# Schematic_RocketTalk_4_6_2021-07-23.net
KiCad netlist of a schematic drawn in EasyEDA
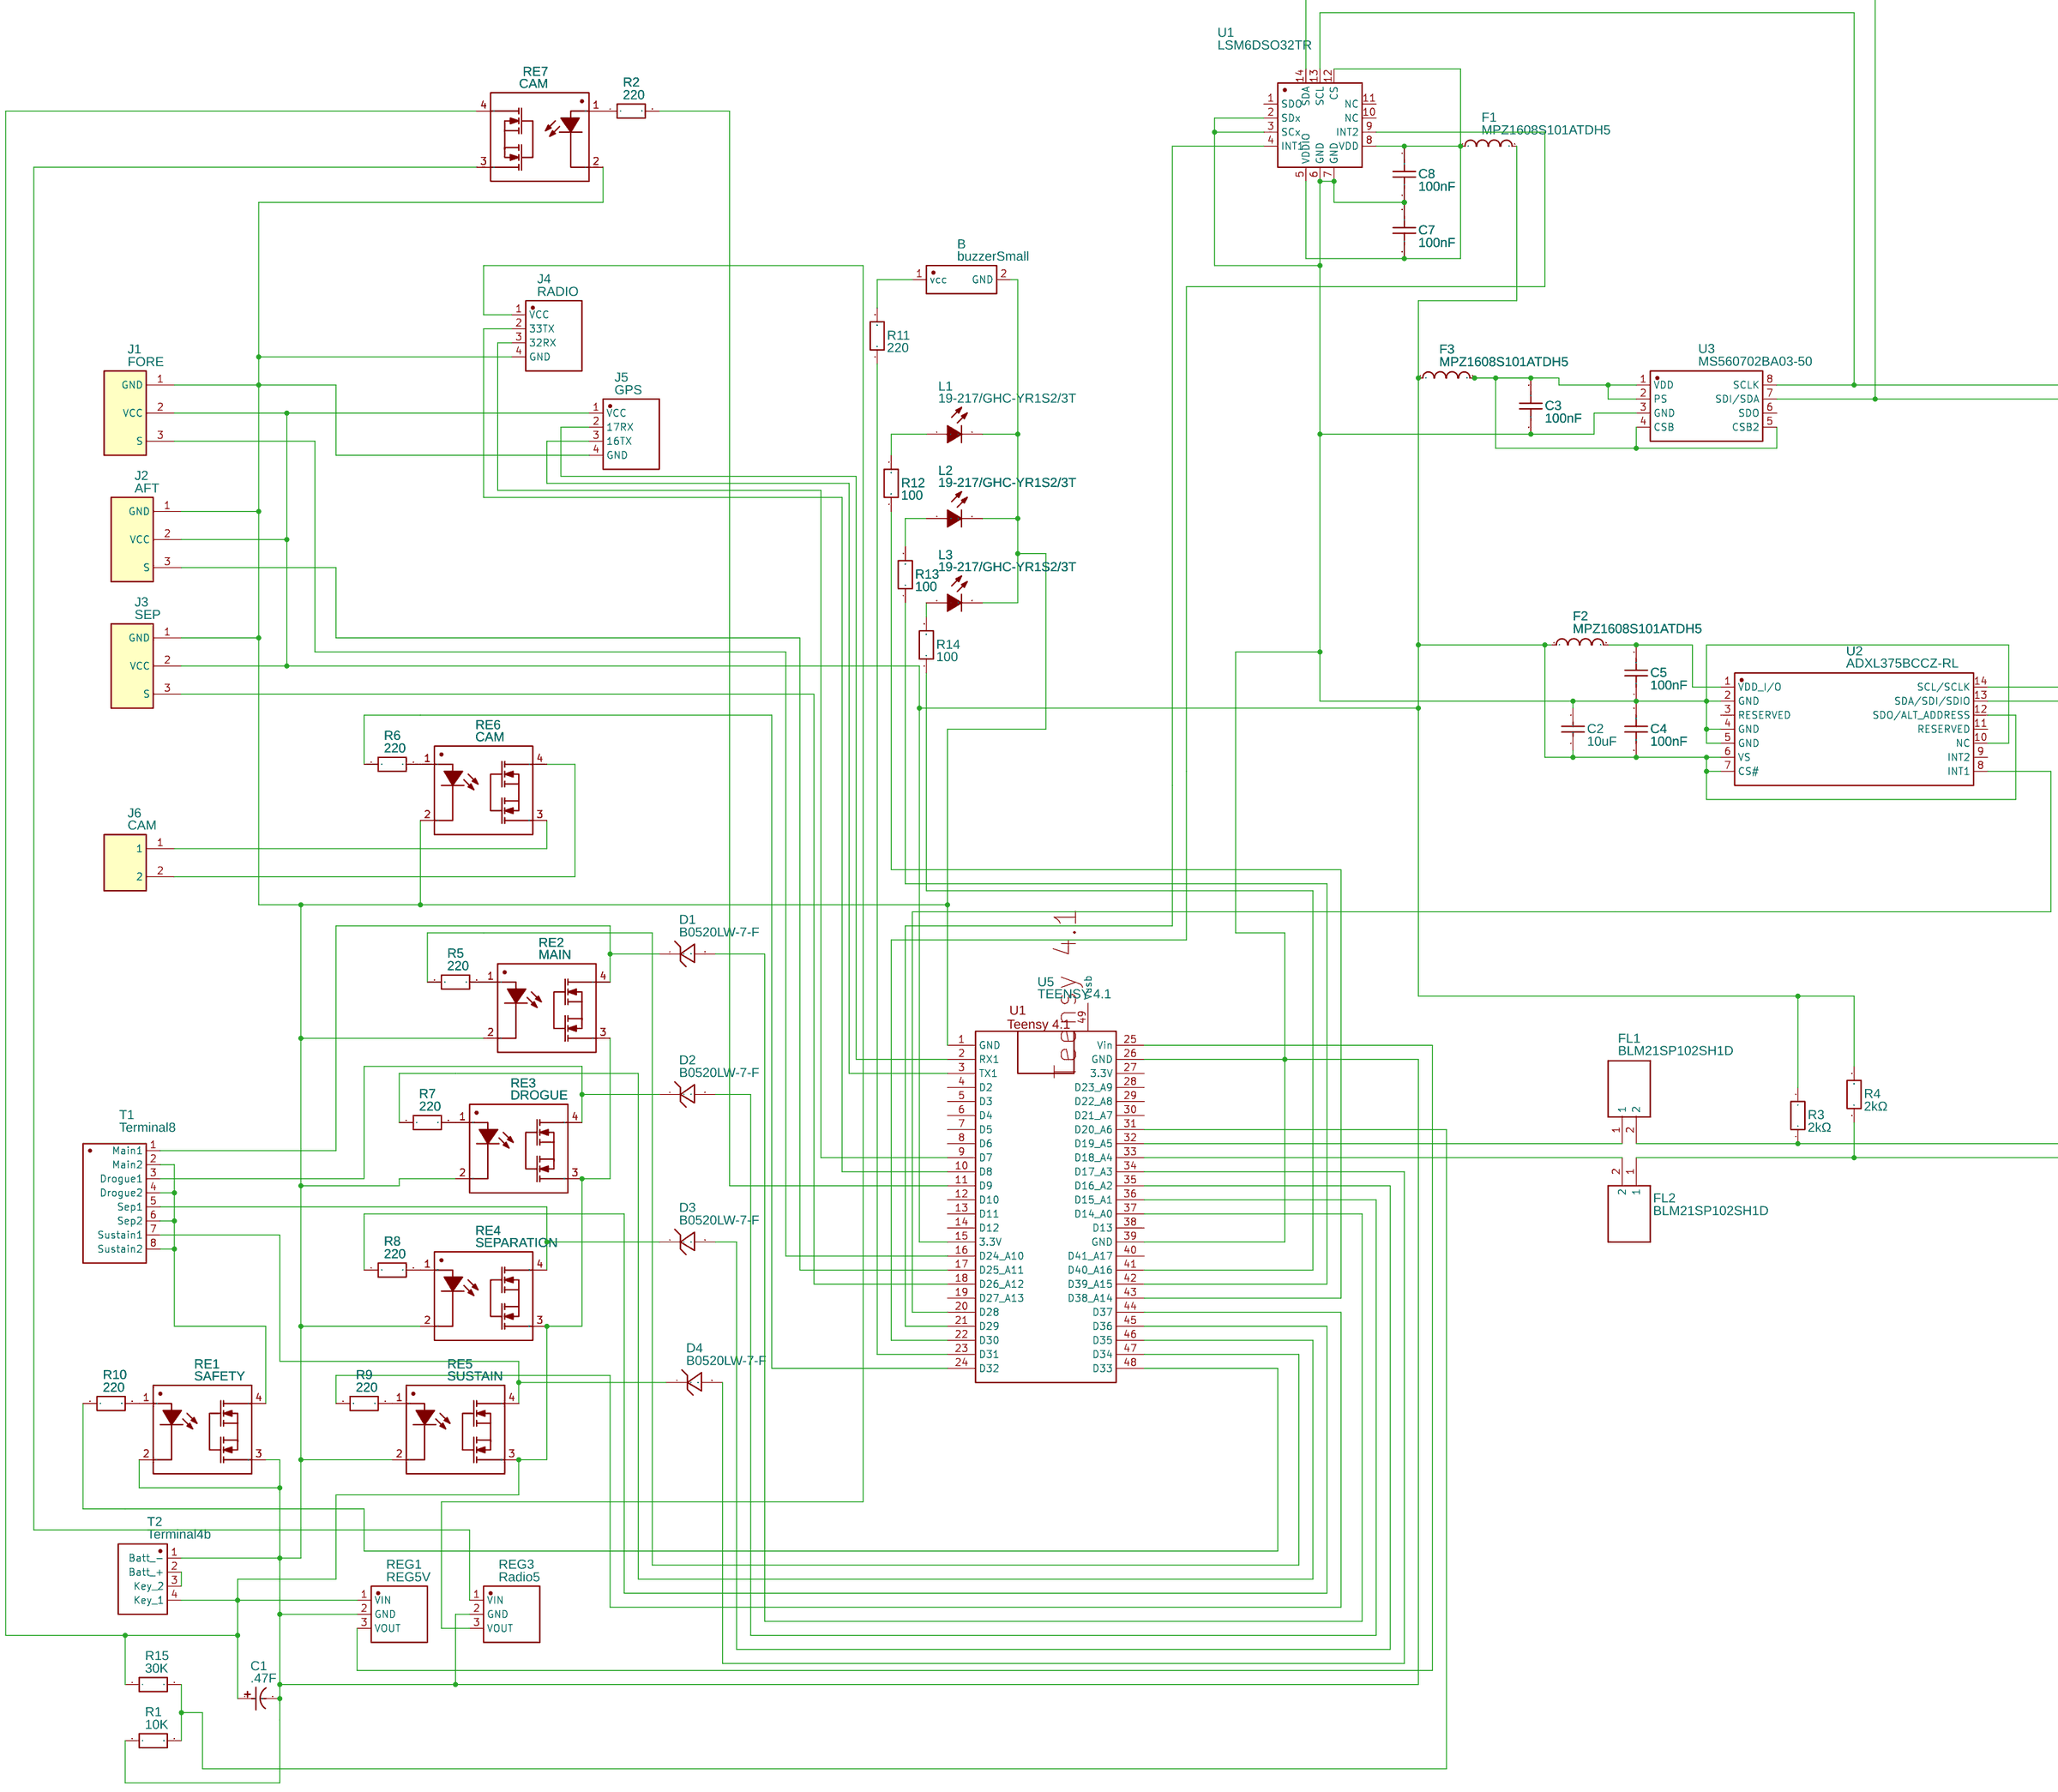
[diagram p0: schematic sheet]

(export (version "E")
  (design (tool "Eeschema 10.0.6"))
  (components
    (comp (ref "B") (value "buzzerSmall") (libsource (lib "") (part "buzzerSmall")))
    (comp (ref "C1")
      (value ".47F")
      (fields
        (field (name "BOM_Manufacturer Part") "SP-5R5-Z224VYA")
        (field (name "BOM_Supplier Part") "C128280")
      )
      (libsource (lib "") (part "SP-5R5-Z224VYA"))
    )
    (comp (ref "C2")
      (value "10uF")
      (fields
        (field (name "BOM_Manufacturer Part") "CL05A106MQ5NUNC")
        (field (name "BOM_Supplier Part") "C15525")
      )
      (libsource (lib "") (part "CL05A106MQ5NUNC"))
    )
    (comp (ref "C3")
      (value "100nF")
      (fields
        (field (name "BOM_Manufacturer Part") "CC0402KRX7R6BB104")
        (field (name "BOM_Supplier Part") "C309458")
      )
      (libsource (lib "") (part "CC0402KRX7R6BB104_1"))
    )
    (comp (ref "C4")
      (value "100nF")
      (fields
        (field (name "BOM_Manufacturer Part") "CC0402KRX7R6BB104")
        (field (name "BOM_Supplier Part") "C309458")
      )
      (libsource (lib "") (part "CC0402KRX7R6BB104"))
    )
    (comp (ref "C5")
      (value "100nF")
      (fields
        (field (name "BOM_Manufacturer Part") "CC0402KRX7R6BB104")
        (field (name "BOM_Supplier Part") "C309458")
      )
      (libsource (lib "") (part "CC0402KRX7R6BB104_1"))
    )
    (comp (ref "C7")
      (value "100nF")
      (fields
        (field (name "BOM_Manufacturer Part") "CC0402KRX7R6BB104")
        (field (name "BOM_Supplier Part") "C309458")
      )
      (libsource (lib "") (part "CC0402KRX7R6BB104"))
    )
    (comp (ref "C8")
      (value "100nF")
      (fields
        (field (name "BOM_Manufacturer Part") "CC0402KRX7R6BB104")
        (field (name "BOM_Supplier Part") "C309458")
      )
      (libsource (lib "") (part "CC0402KRX7R6BB104"))
    )
    (comp (ref "D1")
      (value "B0520LW-7-F")
      (fields (field (name "BOM_Supplier Part") "C155367"))
      (libsource (lib "") (part "B0520LW-7-F"))
    )
    (comp (ref "D2")
      (value "B0520LW-7-F")
      (fields (field (name "BOM_Supplier Part") "C155367"))
      (libsource (lib "") (part "B0520LW-7-F"))
    )
    (comp (ref "D3")
      (value "B0520LW-7-F")
      (fields (field (name "BOM_Supplier Part") "C155367"))
      (libsource (lib "") (part "B0520LW-7-F"))
    )
    (comp (ref "D4")
      (value "B0520LW-7-F")
      (fields (field (name "BOM_Supplier Part") "C155367"))
      (libsource (lib "") (part "B0520LW-7-F"))
    )
    (comp (ref "F1")
      (value "MPZ1608S101ATDH5")
      (fields (field (name "BOM_Supplier Part") "C307769"))
      (libsource (lib "") (part "MPZ1608S101ATDH5"))
    )
    (comp (ref "F2")
      (value "MPZ1608S101ATDH5")
      (fields (field (name "BOM_Supplier Part") "C307769"))
      (libsource (lib "") (part "MPZ1608S101ATDH5"))
    )
    (comp (ref "F3")
      (value "MPZ1608S101ATDH5")
      (fields (field (name "BOM_Supplier Part") "C307769"))
      (libsource (lib "") (part "MPZ1608S101ATDH5"))
    )
    (comp (ref "FL1") (value "BLM21SP102SH1D") (libsource (lib "") (part "BLM21SP102SH1D_1")))
    (comp (ref "FL2") (value "BLM21SP102SH1D") (libsource (lib "") (part "BLM21SP102SH1D")))
    (comp (ref "J1")
      (value "FORE")
      (fields
        (field (name "BOM_Manufacturer Part") "B3B-PH-K-S(LF)(SN)")
        (field (name "BOM_Supplier Part") "C131339")
      )
      (libsource (lib "") (part "Unknown_125_-1020"))
    )
    (comp (ref "J2")
      (value "AFT")
      (fields
        (field (name "BOM_Manufacturer Part") "B3B-PH-K-S(LF)(SN)")
        (field (name "BOM_Supplier Part") "C131339")
      )
      (libsource (lib "") (part "Unknown_130_-930"))
    )
    (comp (ref "J3")
      (value "SEP")
      (fields
        (field (name "BOM_Manufacturer Part") "B3B-PH-K-S(LF)(SN)")
        (field (name "BOM_Supplier Part") "C131339")
      )
      (libsource (lib "") (part "Unknown_130_-840"))
    )
    (comp (ref "J4")
      (value "RADIO")
      (fields
        (field (name "BOM_Manufacturer Part") "B4B-PH-K(LF)(SN)")
        (field (name "BOM_Supplier Part") "C265289")
      )
      (libsource (lib "") (part "Unknown_410_-1080"))
    )
    (comp (ref "J5")
      (value "GPS")
      (fields
        (field (name "BOM_Manufacturer Part") "B4B-PH-K(LF)(SN)")
        (field (name "BOM_Supplier Part") "C265289")
      )
      (libsource (lib "") (part "Unknown_465_-1010"))
    )
    (comp (ref "J6")
      (value "CAM")
      (fields
        (field (name "BOM_Manufacturer Part") "B2B-PH-K-S(LF)(SN)")
        (field (name "BOM_Supplier Part") "C131337")
      )
      (libsource (lib "") (part "B2B-PH-K-S(LF)(SN)"))
    )
    (comp (ref "L1")
      (value "19-217/GHC-YR1S2/3T")
      (fields (field (name "BOM_Supplier Part") "C72043"))
      (libsource (lib "") (part "19-217/GHC-YR1S2/3T"))
    )
    (comp (ref "L2")
      (value "19-217/GHC-YR1S2/3T")
      (fields (field (name "BOM_Supplier Part") "C72043"))
      (libsource (lib "") (part "19-217/GHC-YR1S2/3T"))
    )
    (comp (ref "L3")
      (value "19-217/GHC-YR1S2/3T")
      (fields (field (name "BOM_Supplier Part") "C72043"))
      (libsource (lib "") (part "19-217/GHC-YR1S2/3T"))
    )
    (comp (ref "R1")
      (value "10K")
      (fields
        (field (name "BOM_Manufacturer Part") "ERJP06J221V")
        (field (name "BOM_Supplier Part") "C417010")
      )
      (libsource (lib "") (part "ERJP06J221V"))
    )
    (comp (ref "R2")
      (value "220")
      (fields
        (field (name "BOM_Manufacturer Part") "ERJP06J221V")
        (field (name "BOM_Supplier Part") "C417010")
      )
      (libsource (lib "") (part "ERJP06J221V"))
    )
    (comp (ref "R3")
      (value "2kΩ")
      (fields
        (field (name "BOM_Manufacturer Part") "ERA6AEB202V")
        (field (name "BOM_Supplier Part") "C417117")
      )
      (libsource (lib "") (part "ERA6AEB202V"))
    )
    (comp (ref "R4")
      (value "2kΩ")
      (fields
        (field (name "BOM_Manufacturer Part") "ERA6AEB202V")
        (field (name "BOM_Supplier Part") "C417117")
      )
      (libsource (lib "") (part "ERA6AEB202V"))
    )
    (comp (ref "R5")
      (value "220")
      (fields
        (field (name "BOM_Manufacturer Part") "ERJP06J221V")
        (field (name "BOM_Supplier Part") "C417010")
      )
      (libsource (lib "") (part "ERJP06J221V"))
    )
    (comp (ref "R6")
      (value "220")
      (fields
        (field (name "BOM_Manufacturer Part") "ERJP06J221V")
        (field (name "BOM_Supplier Part") "C417010")
      )
      (libsource (lib "") (part "ERJP06J221V"))
    )
    (comp (ref "R7")
      (value "220")
      (fields
        (field (name "BOM_Manufacturer Part") "ERJP06J221V")
        (field (name "BOM_Supplier Part") "C417010")
      )
      (libsource (lib "") (part "ERJP06J221V"))
    )
    (comp (ref "R8")
      (value "220")
      (fields
        (field (name "BOM_Manufacturer Part") "ERJP06J221V")
        (field (name "BOM_Supplier Part") "C417010")
      )
      (libsource (lib "") (part "ERJP06J221V"))
    )
    (comp (ref "R9")
      (value "220")
      (fields
        (field (name "BOM_Manufacturer Part") "ERJP06J221V")
        (field (name "BOM_Supplier Part") "C417010")
      )
      (libsource (lib "") (part "ERJP06J221V"))
    )
    (comp (ref "R10")
      (value "220")
      (fields
        (field (name "BOM_Manufacturer Part") "ERJP06J221V")
        (field (name "BOM_Supplier Part") "C417010")
      )
      (libsource (lib "") (part "ERJP06J221V"))
    )
    (comp (ref "R11")
      (value "220")
      (fields
        (field (name "BOM_Manufacturer Part") "ERJP06J221V")
        (field (name "BOM_Supplier Part") "C417010")
      )
      (libsource (lib "") (part "ERJP06J221V_1"))
    )
    (comp (ref "R12")
      (value "100")
      (fields
        (field (name "BOM_Manufacturer Part") "ERJP06J221V")
        (field (name "BOM_Supplier Part") "C417010")
      )
      (libsource (lib "") (part "ERJP06J221V_1"))
    )
    (comp (ref "R13")
      (value "100")
      (fields
        (field (name "BOM_Manufacturer Part") "ERJP06J221V")
        (field (name "BOM_Supplier Part") "C417010")
      )
      (libsource (lib "") (part "ERJP06J221V_1"))
    )
    (comp (ref "R14")
      (value "100")
      (fields
        (field (name "BOM_Manufacturer Part") "ERJP06J221V")
        (field (name "BOM_Supplier Part") "C417010")
      )
      (libsource (lib "") (part "ERJP06J221V_1"))
    )
    (comp (ref "R15")
      (value "30K")
      (fields
        (field (name "BOM_Manufacturer Part") "ERJP06J221V")
        (field (name "BOM_Supplier Part") "C417010")
      )
      (libsource (lib "") (part "ERJP06J221V"))
    )
    (comp (ref "RE1")
      (value "SAFETY")
      (fields (field (name "BOM_Manufacturer Part") "AQY210EH") (field (name "BOM_Supplier Part") "C13541"))
      (libsource (lib "") (part "AQY210EH_1"))
    )
    (comp (ref "RE2")
      (value "MAIN")
      (fields (field (name "BOM_Manufacturer Part") "AQY210EH") (field (name "BOM_Supplier Part") "C13541"))
      (libsource (lib "") (part "AQY210EH_1"))
    )
    (comp (ref "RE3")
      (value "DROGUE")
      (fields (field (name "BOM_Manufacturer Part") "AQY210EH") (field (name "BOM_Supplier Part") "C13541"))
      (libsource (lib "") (part "AQY210EH_1"))
    )
    (comp (ref "RE4")
      (value "SEPARATION")
      (fields (field (name "BOM_Manufacturer Part") "AQY210EH") (field (name "BOM_Supplier Part") "C13541"))
      (libsource (lib "") (part "AQY210EH_1"))
    )
    (comp (ref "RE5")
      (value "SUSTAIN")
      (fields (field (name "BOM_Manufacturer Part") "AQY210EH") (field (name "BOM_Supplier Part") "C13541"))
      (libsource (lib "") (part "AQY210EH_1"))
    )
    (comp (ref "RE6")
      (value "CAM")
      (fields (field (name "BOM_Manufacturer Part") "AQY210EH") (field (name "BOM_Supplier Part") "C13541"))
      (libsource (lib "") (part "AQY210EH_1"))
    )
    (comp (ref "RE7")
      (value "CAM")
      (fields (field (name "BOM_Manufacturer Part") "AQY210EH") (field (name "BOM_Supplier Part") "C13541"))
      (libsource (lib "") (part "AQY210EH"))
    )
    (comp (ref "REG1") (value "REG5V") (libsource (lib "") (part "Unknown_310_-165")))
    (comp (ref "REG3") (value "Radio5") (libsource (lib "") (part "Unknown_390_-165")))
    (comp (ref "T1") (value "Terminal8") (libsource (lib "") (part "Terminal8")))
    (comp (ref "T2") (value "Terminal4b") (libsource (lib "") (part "Terminal4b")))
    (comp (ref "U1")
      (value "LSM6DSO32TR")
      (fields (field (name "BOM_Supplier Part") "497-LSM6DSO32TR-ND"))
      (libsource (lib "") (part "LSM6DSO32TR"))
    )
    (comp (ref "U2")
      (value "ADXL375BCCZ-RL")
      (fields (field (name "BOM_Supplier Part") "C662206"))
      (libsource (lib "") (part "ADXL375BCCZ-RL"))
    )
    (comp (ref "U3")
      (value "MS560702BA03-50")
      (fields (field (name "BOM_Supplier Part") "C97627"))
      (libsource (lib "") (part "MS560702BA03-50"))
    )
    (comp (ref "U5") (value "TEENSY 4.1") (libsource (lib "") (part "TEENSY 4.1")))
  )
  (nets
    (net (code "1") (name "Net-(B-GND)") (class "Default")
      (node (ref "B") (pin "2") (pinfunction "GND_2") (pintype "unspecified"))
      (node (ref "C1") (pin "2") (pinfunction "2_2") (pintype "input"))
      (node (ref "C2") (pin "1") (pinfunction "1_1") (pintype "input"))
      (node (ref "C3") (pin "1") (pinfunction "1_1") (pintype "unspecified"))
      (node (ref "C4") (pin "1") (pinfunction "1_1") (pintype "unspecified"))
      (node (ref "C5") (pin "1") (pinfunction "1_1") (pintype "unspecified"))
      (node (ref "C7") (pin "1") (pinfunction "1_1") (pintype "unspecified"))
      (node (ref "C8") (pin "2") (pinfunction "2_2") (pintype "unspecified"))
      (node (ref "J1") (pin "1") (pinfunction "GND_1") (pintype "input"))
      (node (ref "J2") (pin "1") (pinfunction "GND_1") (pintype "input"))
      (node (ref "J3") (pin "1") (pinfunction "GND_1") (pintype "input"))
      (node (ref "J4") (pin "4") (pinfunction "GND_4") (pintype "unspecified"))
      (node (ref "J5") (pin "4") (pinfunction "GND_4") (pintype "unspecified"))
      (node (ref "L1") (pin "2") (pinfunction "C_2") (pintype "input"))
      (node (ref "L2") (pin "2") (pinfunction "C_2") (pintype "input"))
      (node (ref "L3") (pin "2") (pinfunction "C_2") (pintype "input"))
      (node (ref "R1") (pin "1") (pinfunction "1_1") (pintype "unspecified"))
      (node (ref "RE1") (pin "2") (pinfunction "K_2") (pintype "unspecified"))
      (node (ref "RE1") (pin "3") (pinfunction "3_3") (pintype "unspecified"))
      (node (ref "RE2") (pin "2") (pinfunction "K_2") (pintype "unspecified"))
      (node (ref "RE3") (pin "2") (pinfunction "K_2") (pintype "unspecified"))
      (node (ref "RE4") (pin "2") (pinfunction "K_2") (pintype "unspecified"))
      (node (ref "RE5") (pin "2") (pinfunction "K_2") (pintype "unspecified"))
      (node (ref "RE6") (pin "2") (pinfunction "K_2") (pintype "unspecified"))
      (node (ref "RE7") (pin "2") (pinfunction "K_2") (pintype "unspecified"))
      (node (ref "REG1") (pin "2") (pinfunction "GND_2") (pintype "unspecified"))
      (node (ref "REG3") (pin "2") (pinfunction "GND_2") (pintype "unspecified"))
      (node (ref "T2") (pin "1") (pinfunction "Batt_-_1") (pintype "unspecified"))
      (node (ref "U1") (pin "2") (pinfunction "SDx_2") (pintype "unspecified"))
      (node (ref "U1") (pin "3") (pinfunction "SCx_3") (pintype "unspecified"))
      (node (ref "U1") (pin "6") (pinfunction "GND_6") (pintype "unspecified"))
      (node (ref "U1") (pin "7") (pinfunction "GND_7") (pintype "unspecified"))
      (node (ref "U2") (pin "10") (pinfunction "NC_10") (pintype "unspecified"))
      (node (ref "U2") (pin "2") (pinfunction "GND_2") (pintype "unspecified"))
      (node (ref "U2") (pin "4") (pinfunction "GND_4") (pintype "unspecified"))
      (node (ref "U2") (pin "5") (pinfunction "GND_5") (pintype "unspecified"))
      (node (ref "U3") (pin "3") (pinfunction "GND_3") (pintype "unspecified"))
      (node (ref "U5") (pin "1") (pinfunction "GND_1") (pintype "unspecified"))
      (node (ref "U5") (pin "26") (pinfunction "GND_26") (pintype "unspecified"))
      (node (ref "U5") (pin "39") (pinfunction "GND_39") (pintype "unspecified"))
    )
    (net (code "2") (name "Net-(B-vcc)") (class "Default")
      (node (ref "B") (pin "1") (pinfunction "vcc_1") (pintype "unspecified"))
      (node (ref "R11") (pin "2") (pinfunction "2_2") (pintype "unspecified"))
    )
    (net (code "3") (name "Net-(J1-S)") (class "Default")
      (node (ref "J1") (pin "3") (pinfunction "S_3") (pintype "input"))
      (node (ref "U5") (pin "16") (pinfunction "D24_A10_16") (pintype "unspecified"))
    )
    (net (code "4") (name "Net-(J1-VCC)") (class "Default")
      (node (ref "C2") (pin "2") (pinfunction "2_2") (pintype "input"))
      (node (ref "C4") (pin "2") (pinfunction "2_2") (pintype "unspecified"))
      (node (ref "F1") (pin "2") (pinfunction "2_2") (pintype "unspecified"))
      (node (ref "F2") (pin "1") (pinfunction "1_1") (pintype "unspecified"))
      (node (ref "F3") (pin "1") (pinfunction "1_1") (pintype "unspecified"))
      (node (ref "J1") (pin "2") (pinfunction "VCC_2") (pintype "input"))
      (node (ref "J2") (pin "2") (pinfunction "VCC_2") (pintype "input"))
      (node (ref "J3") (pin "2") (pinfunction "VCC_2") (pintype "input"))
      (node (ref "J5") (pin "1") (pinfunction "VCC_1") (pintype "unspecified"))
      (node (ref "R3") (pin "2") (pinfunction "2_2") (pintype "unspecified"))
      (node (ref "R4") (pin "2") (pinfunction "2_2") (pintype "unspecified"))
      (node (ref "U2") (pin "12") (pinfunction "SDO/ALT_ADDRESS_12") (pintype "unspecified"))
      (node (ref "U2") (pin "6") (pinfunction "VS_6") (pintype "unspecified"))
      (node (ref "U2") (pin "7") (pinfunction "CS#_7") (pintype "unspecified"))
      (node (ref "U5") (pin "15") (pinfunction "3.3V_15") (pintype "unspecified"))
    )
    (net (code "5") (name "Net-(J2-S)") (class "Default")
      (node (ref "J2") (pin "3") (pinfunction "S_3") (pintype "input"))
      (node (ref "U5") (pin "17") (pinfunction "D25_A11_17") (pintype "unspecified"))
    )
    (net (code "6") (name "Net-(J3-S)") (class "Default")
      (node (ref "J3") (pin "3") (pinfunction "S_3") (pintype "input"))
      (node (ref "U5") (pin "18") (pinfunction "D26_A12_18") (pintype "unspecified"))
    )
    (net (code "7") (name "Net-(J4-32RX)") (class "Default")
      (node (ref "J4") (pin "3") (pinfunction "32RX_3") (pintype "unspecified"))
      (node (ref "U5") (pin "9") (pinfunction "D7_9") (pintype "unspecified"))
    )
    (net (code "8") (name "Net-(J4-33TX)") (class "Default")
      (node (ref "J4") (pin "2") (pinfunction "33TX_2") (pintype "unspecified"))
      (node (ref "U5") (pin "10") (pinfunction "D8_10") (pintype "unspecified"))
    )
    (net (code "9") (name "Net-(J4-VCC)") (class "Default")
      (node (ref "J4") (pin "1") (pinfunction "VCC_1") (pintype "unspecified"))
      (node (ref "REG3") (pin "3") (pinfunction "VOUT_3") (pintype "unspecified"))
    )
    (net (code "10") (name "Net-(J5-16TX)") (class "Default")
      (node (ref "J5") (pin "3") (pinfunction "16TX_3") (pintype "unspecified"))
      (node (ref "U5") (pin "3") (pinfunction "TX1_3") (pintype "unspecified"))
    )
    (net (code "11") (name "Net-(J5-17RX)") (class "Default")
      (node (ref "J5") (pin "2") (pinfunction "17RX_2") (pintype "unspecified"))
      (node (ref "U5") (pin "2") (pinfunction "RX1_2") (pintype "unspecified"))
    )
    (net (code "12") (name "Net-(J6-Pad1)") (class "Default")
      (node (ref "J6") (pin "1") (pinfunction "1_1") (pintype "input"))
      (node (ref "RE6") (pin "3") (pinfunction "3_3") (pintype "unspecified"))
    )
    (net (code "13") (name "Net-(J6-Pad2)") (class "Default")
      (node (ref "J6") (pin "2") (pinfunction "2_2") (pintype "input"))
      (node (ref "RE6") (pin "4") (pinfunction "4_4") (pintype "unspecified"))
    )
    (net (code "14") (name "Net-(L1-A)") (class "Default")
      (node (ref "L1") (pin "1") (pinfunction "A_1") (pintype "input"))
      (node (ref "R12") (pin "2") (pinfunction "2_2") (pintype "unspecified"))
    )
    (net (code "15") (name "Net-(L2-A)") (class "Default")
      (node (ref "L2") (pin "1") (pinfunction "A_1") (pintype "input"))
      (node (ref "R13") (pin "2") (pinfunction "2_2") (pintype "unspecified"))
    )
    (net (code "16") (name "Net-(L3-A)") (class "Default")
      (node (ref "L3") (pin "1") (pinfunction "A_1") (pintype "input"))
      (node (ref "R14") (pin "2") (pinfunction "2_2") (pintype "unspecified"))
    )
    (net (code "17") (name "Net-(R2-Pad1)") (class "Default")
      (node (ref "R2") (pin "1") (pinfunction "1_1") (pintype "unspecified"))
      (node (ref "RE7") (pin "1") (pinfunction "1_1") (pintype "unspecified"))
    )
    (net (code "18") (name "Net-(R5-Pad2)") (class "Default")
      (node (ref "R5") (pin "2") (pinfunction "2_2") (pintype "unspecified"))
      (node (ref "RE2") (pin "1") (pinfunction "1_1") (pintype "unspecified"))
    )
    (net (code "19") (name "Net-(R6-Pad2)") (class "Default")
      (node (ref "R6") (pin "2") (pinfunction "2_2") (pintype "unspecified"))
      (node (ref "RE6") (pin "1") (pinfunction "1_1") (pintype "unspecified"))
    )
    (net (code "20") (name "Net-(R7-Pad2)") (class "Default")
      (node (ref "R7") (pin "2") (pinfunction "2_2") (pintype "unspecified"))
      (node (ref "RE3") (pin "1") (pinfunction "1_1") (pintype "unspecified"))
    )
    (net (code "21") (name "Net-(R8-Pad2)") (class "Default")
      (node (ref "R8") (pin "2") (pinfunction "2_2") (pintype "unspecified"))
      (node (ref "RE4") (pin "1") (pinfunction "1_1") (pintype "unspecified"))
    )
    (net (code "22") (name "Net-(R9-Pad2)") (class "Default")
      (node (ref "R9") (pin "2") (pinfunction "2_2") (pintype "unspecified"))
      (node (ref "RE5") (pin "1") (pinfunction "1_1") (pintype "unspecified"))
    )
    (net (code "23") (name "Net-(R10-Pad2)") (class "Default")
      (node (ref "R10") (pin "2") (pinfunction "2_2") (pintype "unspecified"))
      (node (ref "RE1") (pin "1") (pinfunction "1_1") (pintype "unspecified"))
    )
    (net (code "24") (name "Net-(REG1-VIN)") (class "Default")
      (node (ref "C1") (pin "1") (pinfunction "1_1") (pintype "input"))
      (node (ref "R15") (pin "1") (pinfunction "1_1") (pintype "unspecified"))
      (node (ref "RE2") (pin "3") (pinfunction "3_3") (pintype "unspecified"))
      (node (ref "RE3") (pin "3") (pinfunction "3_3") (pintype "unspecified"))
      (node (ref "RE4") (pin "3") (pinfunction "3_3") (pintype "unspecified"))
      (node (ref "RE5") (pin "3") (pinfunction "3_3") (pintype "unspecified"))
      (node (ref "RE7") (pin "4") (pinfunction "4_4") (pintype "unspecified"))
      (node (ref "REG1") (pin "1") (pinfunction "VIN_1") (pintype "unspecified"))
      (node (ref "T2") (pin "4") (pinfunction "Key_1_4") (pintype "unspecified"))
    )
    (net (code "25") (name "Net-(REG1-VOUT)") (class "Default")
      (node (ref "REG1") (pin "3") (pinfunction "VOUT_3") (pintype "unspecified"))
      (node (ref "U5") (pin "25") (pinfunction "Vin_25") (pintype "unspecified"))
    )
    (net (code "26") (name "Net-(REG3-VIN)") (class "Default")
      (node (ref "RE7") (pin "3") (pinfunction "3_3") (pintype "unspecified"))
      (node (ref "REG3") (pin "1") (pinfunction "VIN_1") (pintype "unspecified"))
    )
    (net (code "27") (name "Net-(T1-Drogue1)") (class "Default")
      (node (ref "D2") (pin "1") (pinfunction "1_1") (pintype "unspecified"))
      (node (ref "RE3") (pin "4") (pinfunction "4_4") (pintype "unspecified"))
      (node (ref "T1") (pin "3") (pinfunction "Drogue1_3") (pintype "unspecified"))
    )
    (net (code "28") (name "Net-(T1-Drogue2)") (class "Default")
      (node (ref "RE1") (pin "4") (pinfunction "4_4") (pintype "unspecified"))
      (node (ref "T1") (pin "2") (pinfunction "Main2_2") (pintype "unspecified"))
      (node (ref "T1") (pin "4") (pinfunction "Drogue2_4") (pintype "unspecified"))
      (node (ref "T1") (pin "6") (pinfunction "Sep2_6") (pintype "unspecified"))
      (node (ref "T1") (pin "8") (pinfunction "Sustain2_8") (pintype "unspecified"))
    )
    (net (code "29") (name "Net-(T1-Main1)") (class "Default")
      (node (ref "D1") (pin "1") (pinfunction "1_1") (pintype "unspecified"))
      (node (ref "RE2") (pin "4") (pinfunction "4_4") (pintype "unspecified"))
      (node (ref "T1") (pin "1") (pinfunction "Main1_1") (pintype "unspecified"))
    )
    (net (code "30") (name "Net-(T1-Sep1)") (class "Default")
      (node (ref "D3") (pin "1") (pinfunction "1_1") (pintype "unspecified"))
      (node (ref "RE4") (pin "4") (pinfunction "4_4") (pintype "unspecified"))
      (node (ref "T1") (pin "5") (pinfunction "Sep1_5") (pintype "unspecified"))
    )
    (net (code "31") (name "Net-(T1-Sustain1)") (class "Default")
      (node (ref "D4") (pin "1") (pinfunction "1_1") (pintype "unspecified"))
      (node (ref "RE5") (pin "4") (pinfunction "4_4") (pintype "unspecified"))
      (node (ref "T1") (pin "7") (pinfunction "Sustain1_7") (pintype "unspecified"))
    )
    (net (code "32") (name "Net-(T2-Batt_+)") (class "Default")
      (node (ref "T2") (pin "2") (pinfunction "Batt_+_2") (pintype "unspecified"))
      (node (ref "T2") (pin "3") (pinfunction "Key_2_3") (pintype "unspecified"))
    )
    (net (code "33") (name "Net-(U1-CS)") (class "Default")
      (node (ref "C7") (pin "2") (pinfunction "2_2") (pintype "unspecified"))
      (node (ref "C8") (pin "1") (pinfunction "1_1") (pintype "unspecified"))
      (node (ref "F1") (pin "1") (pinfunction "1_1") (pintype "unspecified"))
      (node (ref "U1") (pin "12") (pinfunction "CS_12") (pintype "unspecified"))
      (node (ref "U1") (pin "5") (pinfunction "VDDIO_5") (pintype "unspecified"))
      (node (ref "U1") (pin "8") (pinfunction "VDD_8") (pintype "unspecified"))
    )
    (net (code "34") (name "Net-(U1-INT1)") (class "Default")
      (node (ref "U1") (pin "4") (pinfunction "INT1_4") (pintype "unspecified"))
      (node (ref "U5") (pin "21") (pinfunction "D29_21") (pintype "unspecified"))
    )
    (net (code "35") (name "Net-(U1-INT2)") (class "Default")
      (node (ref "U1") (pin "9") (pinfunction "INT2_9") (pintype "unspecified"))
      (node (ref "U5") (pin "22") (pinfunction "D30_22") (pintype "unspecified"))
    )
    (net (code "36") (name "Net-(U1-SCL)") (class "Default")
      (node (ref "FL1") (pin "2") (pinfunction "2_2") (pintype "bidirectional"))
      (node (ref "R3") (pin "1") (pinfunction "1_1") (pintype "unspecified"))
      (node (ref "U1") (pin "13") (pinfunction "SCL_13") (pintype "unspecified"))
      (node (ref "U2") (pin "14") (pinfunction "SCL/SCLK_14") (pintype "unspecified"))
      (node (ref "U3") (pin "8") (pinfunction "SCLK_8") (pintype "unspecified"))
    )
    (net (code "37") (name "Net-(U1-SDA)") (class "Default")
      (node (ref "FL2") (pin "1") (pinfunction "1_1") (pintype "bidirectional"))
      (node (ref "R4") (pin "1") (pinfunction "1_1") (pintype "unspecified"))
      (node (ref "U1") (pin "14") (pinfunction "SDA_14") (pintype "unspecified"))
      (node (ref "U2") (pin "13") (pinfunction "SDA/SDI/SDIO_13") (pintype "unspecified"))
      (node (ref "U3") (pin "7") (pinfunction "SDI/SDA_7") (pintype "unspecified"))
    )
    (net (code "38") (name "Net-(U2-INT1)") (class "Default")
      (node (ref "U2") (pin "8") (pinfunction "INT1_8") (pintype "unspecified"))
      (node (ref "U5") (pin "20") (pinfunction "D28_20") (pintype "unspecified"))
    )
    (net (code "39") (name "Net-(U2-VDD_I{slash}O)") (class "Default")
      (node (ref "C5") (pin "2") (pinfunction "2_2") (pintype "unspecified"))
      (node (ref "F2") (pin "2") (pinfunction "2_2") (pintype "unspecified"))
      (node (ref "U2") (pin "1") (pinfunction "VDD_I/O_1") (pintype "unspecified"))
    )
    (net (code "40") (name "Net-(U3-CSB)") (class "Default")
      (node (ref "C3") (pin "2") (pinfunction "2_2") (pintype "unspecified"))
      (node (ref "F3") (pin "2") (pinfunction "2_2") (pintype "unspecified"))
      (node (ref "U3") (pin "1") (pinfunction "VDD_1") (pintype "unspecified"))
      (node (ref "U3") (pin "2") (pinfunction "PS_2") (pintype "unspecified"))
      (node (ref "U3") (pin "4") (pinfunction "CSB_4") (pintype "unspecified"))
      (node (ref "U3") (pin "5") (pinfunction "CSB2_5") (pintype "unspecified"))
    )
    (net (code "41") (name "Net-(U5-D9)") (class "Default")
      (node (ref "R2") (pin "2") (pinfunction "2_2") (pintype "unspecified"))
      (node (ref "U5") (pin "11") (pinfunction "D9_11") (pintype "unspecified"))
    )
    (net (code "42") (name "Net-(U5-D14_A0)") (class "Default")
      (node (ref "D1") (pin "2") (pinfunction "2_2") (pintype "unspecified"))
      (node (ref "U5") (pin "37") (pinfunction "D14_A0_37") (pintype "unspecified"))
    )
    (net (code "43") (name "Net-(U5-D15_A1)") (class "Default")
      (node (ref "D2") (pin "2") (pinfunction "2_2") (pintype "unspecified"))
      (node (ref "U5") (pin "36") (pinfunction "D15_A1_36") (pintype "unspecified"))
    )
    (net (code "44") (name "Net-(U5-D16_A2)") (class "Default")
      (node (ref "D3") (pin "2") (pinfunction "2_2") (pintype "unspecified"))
      (node (ref "U5") (pin "35") (pinfunction "D16_A2_35") (pintype "unspecified"))
    )
    (net (code "45") (name "Net-(U5-D17_A3)") (class "Default")
      (node (ref "D4") (pin "2") (pinfunction "2_2") (pintype "unspecified"))
      (node (ref "U5") (pin "34") (pinfunction "D17_A3_34") (pintype "unspecified"))
    )
    (net (code "46") (name "Net-(U5-D18_A4)") (class "Default")
      (node (ref "FL2") (pin "2") (pinfunction "2_2") (pintype "bidirectional"))
      (node (ref "U5") (pin "33") (pinfunction "D18_A4_33") (pintype "unspecified"))
    )
    (net (code "47") (name "Net-(U5-D19_A5)") (class "Default")
      (node (ref "FL1") (pin "1") (pinfunction "1_1") (pintype "bidirectional"))
      (node (ref "U5") (pin "32") (pinfunction "D19_A5_32") (pintype "unspecified"))
    )
    (net (code "48") (name "Net-(U5-D20_A6)") (class "Default")
      (node (ref "R1") (pin "2") (pinfunction "2_2") (pintype "unspecified"))
      (node (ref "R15") (pin "2") (pinfunction "2_2") (pintype "unspecified"))
      (node (ref "U5") (pin "31") (pinfunction "D20_A6_31") (pintype "unspecified"))
    )
    (net (code "49") (name "Net-(U5-D31)") (class "Default")
      (node (ref "R11") (pin "1") (pinfunction "1_1") (pintype "unspecified"))
      (node (ref "U5") (pin "23") (pinfunction "D31_23") (pintype "unspecified"))
    )
    (net (code "50") (name "Net-(U5-D32)") (class "Default")
      (node (ref "R6") (pin "1") (pinfunction "1_1") (pintype "unspecified"))
      (node (ref "U5") (pin "24") (pinfunction "D32_24") (pintype "unspecified"))
    )
    (net (code "51") (name "Net-(U5-D33)") (class "Default")
      (node (ref "R10") (pin "1") (pinfunction "1_1") (pintype "unspecified"))
      (node (ref "U5") (pin "48") (pinfunction "D33_48") (pintype "unspecified"))
    )
    (net (code "52") (name "Net-(U5-D34)") (class "Default")
      (node (ref "R5") (pin "1") (pinfunction "1_1") (pintype "unspecified"))
      (node (ref "U5") (pin "47") (pinfunction "D34_47") (pintype "unspecified"))
    )
    (net (code "53") (name "Net-(U5-D35)") (class "Default")
      (node (ref "R7") (pin "1") (pinfunction "1_1") (pintype "unspecified"))
      (node (ref "U5") (pin "46") (pinfunction "D35_46") (pintype "unspecified"))
    )
    (net (code "54") (name "Net-(U5-D36)") (class "Default")
      (node (ref "R8") (pin "1") (pinfunction "1_1") (pintype "unspecified"))
      (node (ref "U5") (pin "45") (pinfunction "D36_45") (pintype "unspecified"))
    )
    (net (code "55") (name "Net-(U5-D37)") (class "Default")
      (node (ref "R9") (pin "1") (pinfunction "1_1") (pintype "unspecified"))
      (node (ref "U5") (pin "44") (pinfunction "D37_44") (pintype "unspecified"))
    )
    (net (code "56") (name "Net-(U5-D38_A14)") (class "Default")
      (node (ref "R12") (pin "1") (pinfunction "1_1") (pintype "unspecified"))
      (node (ref "U5") (pin "43") (pinfunction "D38_A14_43") (pintype "unspecified"))
    )
    (net (code "57") (name "Net-(U5-D39_A15)") (class "Default")
      (node (ref "R13") (pin "1") (pinfunction "1_1") (pintype "unspecified"))
      (node (ref "U5") (pin "42") (pinfunction "D39_A15_42") (pintype "unspecified"))
    )
    (net (code "58") (name "Net-(U5-D40_A16)") (class "Default")
      (node (ref "R14") (pin "1") (pinfunction "1_1") (pintype "unspecified"))
      (node (ref "U5") (pin "41") (pinfunction "D40_A16_41") (pintype "unspecified"))
    )
    (net (code "59") (name "unconnected-(U1-NC-Pad10)") (class "Default")
      (node (ref "U1") (pin "10") (pinfunction "NC_10") (pintype "unspecified"))
    )
    (net (code "60") (name "unconnected-(U1-NC-Pad11)") (class "Default")
      (node (ref "U1") (pin "11") (pinfunction "NC_11") (pintype "unspecified"))
    )
    (net (code "61") (name "unconnected-(U1-SDO-Pad1)") (class "Default")
      (node (ref "U1") (pin "1") (pinfunction "SDO_1") (pintype "unspecified"))
    )
    (net (code "62") (name "unconnected-(U2-INT2-Pad9)") (class "Default")
      (node (ref "U2") (pin "9") (pinfunction "INT2_9") (pintype "unspecified"))
    )
    (net (code "63") (name "unconnected-(U2-RESERVED-Pad3)") (class "Default")
      (node (ref "U2") (pin "3") (pinfunction "RESERVED_3") (pintype "unspecified"))
    )
    (net (code "64") (name "unconnected-(U2-RESERVED-Pad11)") (class "Default")
      (node (ref "U2") (pin "11") (pinfunction "RESERVED_11") (pintype "unspecified"))
    )
    (net (code "65") (name "unconnected-(U3-SDO-Pad6)") (class "Default")
      (node (ref "U3") (pin "6") (pinfunction "SDO_6") (pintype "unspecified"))
    )
    (net (code "66") (name "unconnected-(U5-3.3V-Pad27)") (class "Default")
      (node (ref "U5") (pin "27") (pinfunction "3.3V_27") (pintype "unspecified"))
    )
    (net (code "67") (name "unconnected-(U5-D2-Pad4)") (class "Default")
      (node (ref "U5") (pin "4") (pinfunction "D2_4") (pintype "unspecified"))
    )
    (net (code "68") (name "unconnected-(U5-D3-Pad5)") (class "Default")
      (node (ref "U5") (pin "5") (pinfunction "D3_5") (pintype "unspecified"))
    )
    (net (code "69") (name "unconnected-(U5-D4-Pad6)") (class "Default")
      (node (ref "U5") (pin "6") (pinfunction "D4_6") (pintype "unspecified"))
    )
    (net (code "70") (name "unconnected-(U5-D5-Pad7)") (class "Default")
      (node (ref "U5") (pin "7") (pinfunction "D5_7") (pintype "unspecified"))
    )
    (net (code "71") (name "unconnected-(U5-D6-Pad8)") (class "Default")
      (node (ref "U5") (pin "8") (pinfunction "D6_8") (pintype "unspecified"))
    )
    (net (code "72") (name "unconnected-(U5-D10-Pad12)") (class "Default")
      (node (ref "U5") (pin "12") (pinfunction "D10_12") (pintype "unspecified"))
    )
    (net (code "73") (name "unconnected-(U5-D11-Pad13)") (class "Default")
      (node (ref "U5") (pin "13") (pinfunction "D11_13") (pintype "unspecified"))
    )
    (net (code "74") (name "unconnected-(U5-D12-Pad14)") (class "Default")
      (node (ref "U5") (pin "14") (pinfunction "D12_14") (pintype "unspecified"))
    )
    (net (code "75") (name "unconnected-(U5-D13-Pad38)") (class "Default")
      (node (ref "U5") (pin "38") (pinfunction "D13_38") (pintype "unspecified"))
    )
    (net (code "76") (name "unconnected-(U5-D21_A7-Pad30)") (class "Default")
      (node (ref "U5") (pin "30") (pinfunction "D21_A7_30") (pintype "unspecified"))
    )
    (net (code "77") (name "unconnected-(U5-D22_A8-Pad29)") (class "Default")
      (node (ref "U5") (pin "29") (pinfunction "D22_A8_29") (pintype "unspecified"))
    )
    (net (code "78") (name "unconnected-(U5-D23_A9-Pad28)") (class "Default")
      (node (ref "U5") (pin "28") (pinfunction "D23_A9_28") (pintype "unspecified"))
    )
    (net (code "79") (name "unconnected-(U5-D27_A13-Pad19)") (class "Default")
      (node (ref "U5") (pin "19") (pinfunction "D27_A13_19") (pintype "unspecified"))
    )
    (net (code "80") (name "unconnected-(U5-D41_A17-Pad40)") (class "Default")
      (node (ref "U5") (pin "40") (pinfunction "D41_A17_40") (pintype "unspecified"))
    )
    (net (code "81") (name "unconnected-(U5-Vusb-Pad49)") (class "Default")
      (node (ref "U5") (pin "49") (pinfunction "Vusb_49") (pintype "unspecified"))
    )
  )
)
